# plant.net
KiCad netlist of a schematic drawn in EAGLE
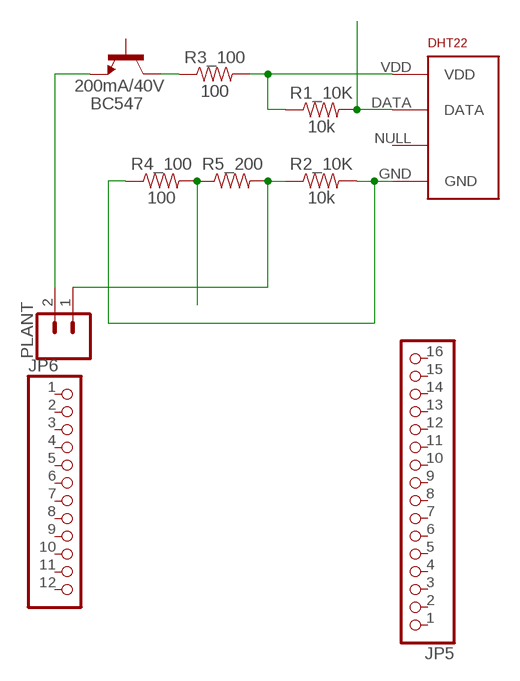
[diagram p0: schematic, sheet 1]

(export (version "E")
  (design (tool "Eeschema 10.0.6"))
  (components
    (comp (ref "BC547")
      (value "200mA/40V")
      (footprint "eagle-import:TO-92")
      (libsource (lib "eagle-import") (part "TRANS_NPN-2N3904"))
    )
    (comp (ref "DHT22")
      (value "RHT03_DHT-22_AM2302")
      (footprint "eagle-import:RHT03_DHT-22")
      (libsource (lib "eagle-import") (part "RHT03_DHT-22_AM2302"))
    )
    (comp (ref "JP5")
      (value "HEADER-1X16ROUND")
      (footprint "eagle-import:1X16_ROUND")
      (libsource (lib "eagle-import") (part "HEADER-1X16ROUND"))
    )
    (comp (ref "JP6")
      (value "HEADER-1X12")
      (footprint "eagle-import:1X12_ROUND")
      (libsource (lib "eagle-import") (part "HEADER-1X12"))
    )
    (comp (ref "PLANT")
      (value "CONN_02")
      (footprint "eagle-import:1X02")
      (libsource (lib "eagle-import") (part "CONN_02"))
    )
    (comp (ref "R1_10K")
      (value "10k")
      (footprint "eagle-import:AXIAL-0.3")
      (libsource (lib "eagle-import") (part "10KOHM-HORIZ-1/4W-1%"))
    )
    (comp (ref "R2_10K")
      (value "10k")
      (footprint "eagle-import:AXIAL-0.3")
      (libsource (lib "eagle-import") (part "10KOHM-HORIZ-1/4W-1%"))
    )
    (comp (ref "R3_100")
      (value "100")
      (footprint "eagle-import:AXIAL-0.3")
      (libsource (lib "eagle-import") (part "100OHM-HORIZ-1/4W-1%"))
    )
    (comp (ref "R4_100")
      (value "100")
      (footprint "eagle-import:AXIAL-0.3")
      (libsource (lib "eagle-import") (part "100OHM-HORIZ-1/4W-1%"))
    )
    (comp (ref "R5_200")
      (value "RESISTORAXIAL-0.3")
      (footprint "eagle-import:AXIAL-0.3")
      (libsource (lib "eagle-import") (part "RESISTORAXIAL-0.3"))
    )
  )
  (nets
    (net (code "1") (name "Net-(BC547-C)") (class "Default")
      (node (ref "BC547") (pin "3") (pinfunction "C_3") (pintype "passive"))
      (node (ref "R3_100") (pin "P$1") (pinfunction "1_P$1") (pintype "passive"))
    )
    (net (code "2") (name "Net-(BC547-E)") (class "Default")
      (node (ref "BC547") (pin "1") (pinfunction "E_1") (pintype "passive"))
      (node (ref "PLANT") (pin "2") (pinfunction "2_2") (pintype "passive"))
    )
    (net (code "3") (name "Net-(R1_10K-1)") (class "Default")
      (node (ref "DHT22") (pin "VDD") (pinfunction "VDD_VDD") (pintype "power_in"))
      (node (ref "R1_10K") (pin "P$1") (pinfunction "1_P$1") (pintype "passive"))
      (node (ref "R3_100") (pin "P$2") (pinfunction "2_P$2") (pintype "passive"))
    )
    (net (code "4") (name "Net-(R1_10K-2)") (class "Default")
      (node (ref "DHT22") (pin "DATA") (pinfunction "DATA_DATA") (pintype "bidirectional"))
      (node (ref "R1_10K") (pin "P$2") (pinfunction "2_P$2") (pintype "passive"))
    )
    (net (code "5") (name "Net-(R2_10K-1)") (class "Default")
      (node (ref "PLANT") (pin "1") (pinfunction "1_1") (pintype "passive"))
      (node (ref "R2_10K") (pin "P$1") (pinfunction "1_P$1") (pintype "passive"))
      (node (ref "R5_200") (pin "P$2") (pinfunction "2_P$2") (pintype "passive"))
    )
    (net (code "6") (name "Net-(R2_10K-2)") (class "Default")
      (node (ref "DHT22") (pin "GND") (pinfunction "GND_GND") (pintype "power_in"))
      (node (ref "R2_10K") (pin "P$2") (pinfunction "2_P$2") (pintype "passive"))
      (node (ref "R4_100") (pin "P$1") (pinfunction "1_P$1") (pintype "passive"))
    )
    (net (code "7") (name "Net-(R4_100-2)") (class "Default")
      (node (ref "R4_100") (pin "P$2") (pinfunction "2_P$2") (pintype "passive"))
      (node (ref "R5_200") (pin "P$1") (pinfunction "1_P$1") (pintype "passive"))
    )
    (net (code "8") (name "unconnected-(BC547-B-Pad2)") (class "Default")
      (node (ref "BC547") (pin "2") (pinfunction "B_2") (pintype "passive"))
    )
    (net (code "9") (name "unconnected-(DHT22-PadNULL)") (class "Default")
      (node (ref "DHT22") (pin "NULL") (pinfunction "NULL_NULL") (pintype "no_connect"))
    )
    (net (code "10") (name "unconnected-(JP5-Pad1)") (class "Default")
      (node (ref "JP5") (pin "1") (pinfunction "1_1") (pintype "passive"))
    )
    (net (code "11") (name "unconnected-(JP5-Pad2)") (class "Default")
      (node (ref "JP5") (pin "2") (pinfunction "2_2") (pintype "passive"))
    )
    (net (code "12") (name "unconnected-(JP5-Pad3)") (class "Default")
      (node (ref "JP5") (pin "3") (pinfunction "3_3") (pintype "passive"))
    )
    (net (code "13") (name "unconnected-(JP5-Pad4)") (class "Default")
      (node (ref "JP5") (pin "4") (pinfunction "4_4") (pintype "passive"))
    )
    (net (code "14") (name "unconnected-(JP5-Pad5)") (class "Default")
      (node (ref "JP5") (pin "5") (pinfunction "5_5") (pintype "passive"))
    )
    (net (code "15") (name "unconnected-(JP5-Pad6)") (class "Default")
      (node (ref "JP5") (pin "6") (pinfunction "6_6") (pintype "passive"))
    )
    (net (code "16") (name "unconnected-(JP5-Pad7)") (class "Default")
      (node (ref "JP5") (pin "7") (pinfunction "7_7") (pintype "passive"))
    )
    (net (code "17") (name "unconnected-(JP5-Pad8)") (class "Default")
      (node (ref "JP5") (pin "8") (pinfunction "8_8") (pintype "passive"))
    )
    (net (code "18") (name "unconnected-(JP5-Pad9)") (class "Default")
      (node (ref "JP5") (pin "9") (pinfunction "9_9") (pintype "passive"))
    )
    (net (code "19") (name "unconnected-(JP5-Pad10)") (class "Default")
      (node (ref "JP5") (pin "10") (pinfunction "10_10") (pintype "passive"))
    )
    (net (code "20") (name "unconnected-(JP5-Pad11)") (class "Default")
      (node (ref "JP5") (pin "11") (pinfunction "11_11") (pintype "passive"))
    )
    (net (code "21") (name "unconnected-(JP5-Pad12)") (class "Default")
      (node (ref "JP5") (pin "12") (pinfunction "12_12") (pintype "passive"))
    )
    (net (code "22") (name "unconnected-(JP5-Pad13)") (class "Default")
      (node (ref "JP5") (pin "13") (pinfunction "13_13") (pintype "passive"))
    )
    (net (code "23") (name "unconnected-(JP5-Pad14)") (class "Default")
      (node (ref "JP5") (pin "14") (pinfunction "14_14") (pintype "passive"))
    )
    (net (code "24") (name "unconnected-(JP5-Pad15)") (class "Default")
      (node (ref "JP5") (pin "15") (pinfunction "15_15") (pintype "passive"))
    )
    (net (code "25") (name "unconnected-(JP5-Pad16)") (class "Default")
      (node (ref "JP5") (pin "16") (pinfunction "16_16") (pintype "passive"))
    )
    (net (code "26") (name "unconnected-(JP6-Pad1)") (class "Default")
      (node (ref "JP6") (pin "1") (pinfunction "1_1") (pintype "passive"))
    )
    (net (code "27") (name "unconnected-(JP6-Pad2)") (class "Default")
      (node (ref "JP6") (pin "2") (pinfunction "2_2") (pintype "passive"))
    )
    (net (code "28") (name "unconnected-(JP6-Pad3)") (class "Default")
      (node (ref "JP6") (pin "3") (pinfunction "3_3") (pintype "passive"))
    )
    (net (code "29") (name "unconnected-(JP6-Pad4)") (class "Default")
      (node (ref "JP6") (pin "4") (pinfunction "4_4") (pintype "passive"))
    )
    (net (code "30") (name "unconnected-(JP6-Pad5)") (class "Default")
      (node (ref "JP6") (pin "5") (pinfunction "5_5") (pintype "passive"))
    )
    (net (code "31") (name "unconnected-(JP6-Pad6)") (class "Default")
      (node (ref "JP6") (pin "6") (pinfunction "6_6") (pintype "passive"))
    )
    (net (code "32") (name "unconnected-(JP6-Pad7)") (class "Default")
      (node (ref "JP6") (pin "7") (pinfunction "7_7") (pintype "passive"))
    )
    (net (code "33") (name "unconnected-(JP6-Pad8)") (class "Default")
      (node (ref "JP6") (pin "8") (pinfunction "8_8") (pintype "passive"))
    )
    (net (code "34") (name "unconnected-(JP6-Pad9)") (class "Default")
      (node (ref "JP6") (pin "9") (pinfunction "9_9") (pintype "passive"))
    )
    (net (code "35") (name "unconnected-(JP6-Pad10)") (class "Default")
      (node (ref "JP6") (pin "10") (pinfunction "10_10") (pintype "passive"))
    )
    (net (code "36") (name "unconnected-(JP6-Pad11)") (class "Default")
      (node (ref "JP6") (pin "11") (pinfunction "11_11") (pintype "passive"))
    )
    (net (code "37") (name "unconnected-(JP6-Pad12)") (class "Default")
      (node (ref "JP6") (pin "12") (pinfunction "12_12") (pintype "passive"))
    )
  )
)
